# PhotoResistor.net
KiCad netlist of a schematic drawn in Altium Designer
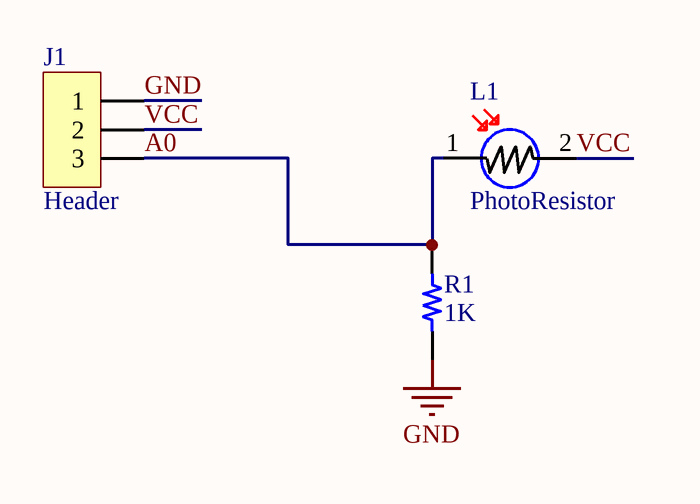
[diagram p0: PhotoResistor.SchDoc]

(export (version "E")
  (design (tool "Eeschema 10.0.6"))
  (components
    (comp (ref "J1")
      (value "Header")
      (footprint "MOLEX SDA-70553-3PIN")
      (libsource (lib "Connectors") (part "3 Pin"))
    )
    (comp (ref "L1")
      (value "PhotoResistor")
      (footprint "PhotoResistor")
      (libsource (lib "Sensors") (part "PhotoResistor"))
    )
    (comp (ref "R1")
      (value "1K")
      (footprint "RES 1206/3216")
      (description "SMT Resistor")
      (libsource (lib "Cap_Res") (part "Resistor"))
    )
  )
  (nets
    (net (code "1") (name "/A0") (class "Default")
      (node (ref "J1") (pin "3") (pinfunction "3_3") (pintype "passive"))
      (node (ref "L1") (pin "1") (pinfunction "1_1") (pintype "passive"))
      (node (ref "R1") (pin "2") (pinfunction "2_2") (pintype "passive"))
    )
    (net (code "2") (name "/VCC") (class "Default")
      (node (ref "J1") (pin "2") (pinfunction "2_2") (pintype "passive"))
      (node (ref "L1") (pin "2") (pinfunction "2_2") (pintype "passive"))
    )
    (net (code "3") (name "GND") (class "Default")
      (node (ref "J1") (pin "1") (pinfunction "1_1") (pintype "passive"))
      (node (ref "R1") (pin "1") (pinfunction "1_1") (pintype "passive"))
    )
  )
)
